# NE555TEST.net
KiCad netlist of a schematic drawn in EAGLE
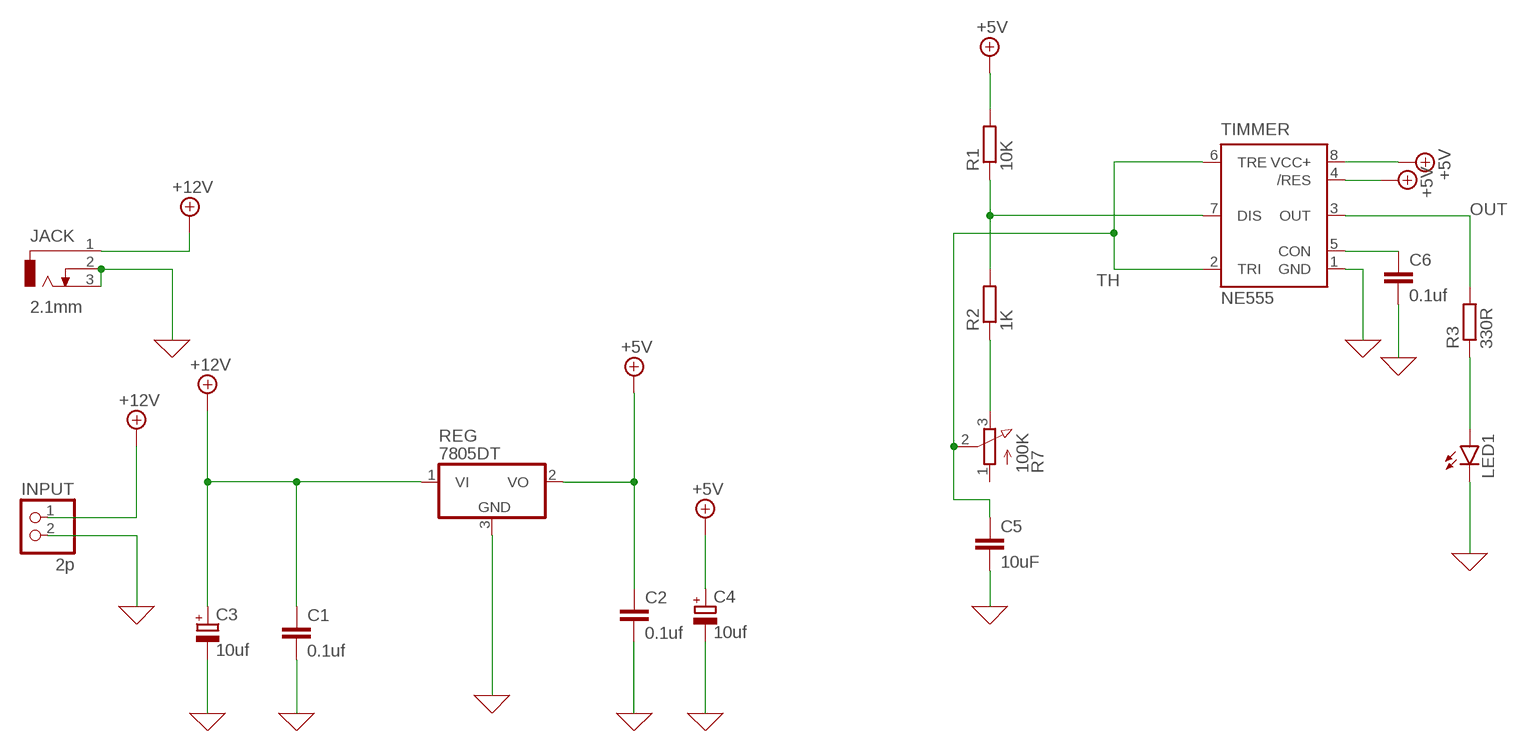
[diagram p0: schematic, sheet 1]

(export (version "E")
  (design (tool "Eeschema 10.0.6"))
  (components
    (comp (ref "C1")
      (value "0.1uf")
      (footprint "eagle-import:C050-030X075")
      (libsource (lib "eagle-import") (part "C-EU050-030X075"))
    )
    (comp (ref "C2")
      (value "0.1uf")
      (footprint "eagle-import:C050-030X075")
      (libsource (lib "eagle-import") (part "C-EU050-030X075"))
    )
    (comp (ref "C3")
      (value "10uf")
      (footprint "eagle-import:E3,5-8")
      (libsource (lib "eagle-import") (part "CPOL-EUE3.5-8"))
    )
    (comp (ref "C4")
      (value "10uf")
      (footprint "eagle-import:E3,5-8")
      (libsource (lib "eagle-import") (part "CPOL-EUE3.5-8"))
    )
    (comp (ref "C5")
      (value "10uF")
      (footprint "eagle-import:C050-030X075")
      (libsource (lib "eagle-import") (part "C-EU050-030X075"))
    )
    (comp (ref "C6")
      (value "0.1uf")
      (footprint "eagle-import:C050-030X075")
      (libsource (lib "eagle-import") (part "C-EU050-030X075"))
    )
    (comp (ref "INPUT")
      (value "2p")
      (footprint "eagle-import:1X02")
      (libsource (lib "eagle-import") (part "PINHD-1X2"))
    )
    (comp (ref "JACK")
      (value "2.1mm")
      (footprint "eagle-import:DCJ0202")
      (libsource (lib "eagle-import") (part "DCJ0202"))
    )
    (comp (ref "LED1")
      (value "LED3MM")
      (footprint "eagle-import:LED3MM")
      (libsource (lib "eagle-import") (part "LED3MM"))
    )
    (comp (ref "R1")
      (value "10K")
      (footprint "eagle-import:0207_10")
      (libsource (lib "eagle-import") (part "R-EU_0207/10"))
    )
    (comp (ref "R2")
      (value "1K")
      (footprint "eagle-import:0207_10")
      (libsource (lib "eagle-import") (part "R-EU_0207/10"))
    )
    (comp (ref "R3")
      (value "330R")
      (footprint "eagle-import:0207_10")
      (libsource (lib "eagle-import") (part "R-EU_0207/10"))
    )
    (comp (ref "R7")
      (value "100K")
      (footprint "eagle-import:3RP_1610N")
      (libsource (lib "eagle-import") (part "3RP/1610N"))
    )
    (comp (ref "REG")
      (value "7805DT")
      (footprint "eagle-import:TO252")
      (libsource (lib "eagle-import") (part "78DT05"))
    )
    (comp (ref "TIMMER")
      (value "NE555")
      (footprint "eagle-import:DIL-08")
      (fields (field (name "MF") "Arrow Electronics") (field (name "MPN") "NE555N"))
      (libsource (lib "eagle-import") (part "NE555"))
    )
  )
  (nets
    (net (code "1") (name "+5V") (class "Default")
      (node (ref "C2") (pin "1") (pinfunction "1_1") (pintype "passive"))
      (node (ref "C4") (pin "+") (pinfunction "+_+") (pintype "passive"))
      (node (ref "R1") (pin "2") (pinfunction "2_2") (pintype "passive"))
      (node (ref "REG") (pin "2") (pinfunction "VO_2") (pintype "passive"))
      (node (ref "TIMMER") (pin "4") (pinfunction "/RES_4") (pintype "input"))
      (node (ref "TIMMER") (pin "8") (pinfunction "VCC+_8") (pintype "power_in"))
    )
    (net (code "2") (name "+12V") (class "Default")
      (node (ref "C1") (pin "1") (pinfunction "1_1") (pintype "passive"))
      (node (ref "C3") (pin "+") (pinfunction "+_+") (pintype "passive"))
      (node (ref "INPUT") (pin "1") (pinfunction "1_1") (pintype "passive"))
      (node (ref "JACK") (pin "1") (pinfunction "1_1") (pintype "passive"))
      (node (ref "REG") (pin "1") (pinfunction "VI_1") (pintype "input"))
    )
    (net (code "3") (name "/OUT") (class "Default")
      (node (ref "R3") (pin "2") (pinfunction "2_2") (pintype "passive"))
      (node (ref "TIMMER") (pin "3") (pinfunction "OUT_3") (pintype "output"))
    )
    (net (code "4") (name "/TH") (class "Default")
      (node (ref "C5") (pin "1") (pinfunction "1_1") (pintype "passive"))
      (node (ref "R7") (pin "2") (pinfunction "S_2") (pintype "passive"))
      (node (ref "TIMMER") (pin "2") (pinfunction "TRI_2") (pintype "input"))
      (node (ref "TIMMER") (pin "6") (pinfunction "TRE_6") (pintype "input"))
    )
    (net (code "5") (name "GND") (class "Default")
      (node (ref "C1") (pin "2") (pinfunction "2_2") (pintype "passive"))
      (node (ref "C2") (pin "2") (pinfunction "2_2") (pintype "passive"))
      (node (ref "C3") (pin "-") (pinfunction "-_-") (pintype "passive"))
      (node (ref "C4") (pin "-") (pinfunction "-_-") (pintype "passive"))
      (node (ref "C5") (pin "2") (pinfunction "2_2") (pintype "passive"))
      (node (ref "C6") (pin "2") (pinfunction "2_2") (pintype "passive"))
      (node (ref "INPUT") (pin "2") (pinfunction "2_2") (pintype "passive"))
      (node (ref "JACK") (pin "2") (pinfunction "2_2") (pintype "passive"))
      (node (ref "JACK") (pin "3") (pinfunction "3_3") (pintype "passive"))
      (node (ref "LED1") (pin "K") (pinfunction "C_K") (pintype "passive"))
      (node (ref "REG") (pin "3") (pinfunction "GND_3") (pintype "passive"))
      (node (ref "TIMMER") (pin "1") (pinfunction "GND_1") (pintype "power_in"))
    )
    (net (code "6") (name "Net-(LED1-PadA)") (class "Default")
      (node (ref "LED1") (pin "A") (pinfunction "A_A") (pintype "passive"))
      (node (ref "R3") (pin "1") (pinfunction "1_1") (pintype "passive"))
    )
    (net (code "7") (name "Net-(R7-E)") (class "Default")
      (node (ref "R2") (pin "1") (pinfunction "1_1") (pintype "passive"))
      (node (ref "R7") (pin "3") (pinfunction "E_3") (pintype "passive"))
    )
    (net (code "8") (name "Net-(TIMMER-CON)") (class "Default")
      (node (ref "C6") (pin "1") (pinfunction "1_1") (pintype "passive"))
      (node (ref "TIMMER") (pin "5") (pinfunction "CON_5") (pintype "input"))
    )
    (net (code "9") (name "Net-(TIMMER-DIS)") (class "Default")
      (node (ref "R1") (pin "1") (pinfunction "1_1") (pintype "passive"))
      (node (ref "R2") (pin "2") (pinfunction "2_2") (pintype "passive"))
      (node (ref "TIMMER") (pin "7") (pinfunction "DIS_7") (pintype "input"))
    )
    (net (code "10") (name "unconnected-(R7-A-Pad1)") (class "Default")
      (node (ref "R7") (pin "1") (pinfunction "A_1") (pintype "passive"))
    )
  )
)
